# transmitter.net
KiCad netlist of a schematic drawn in Altium Designer
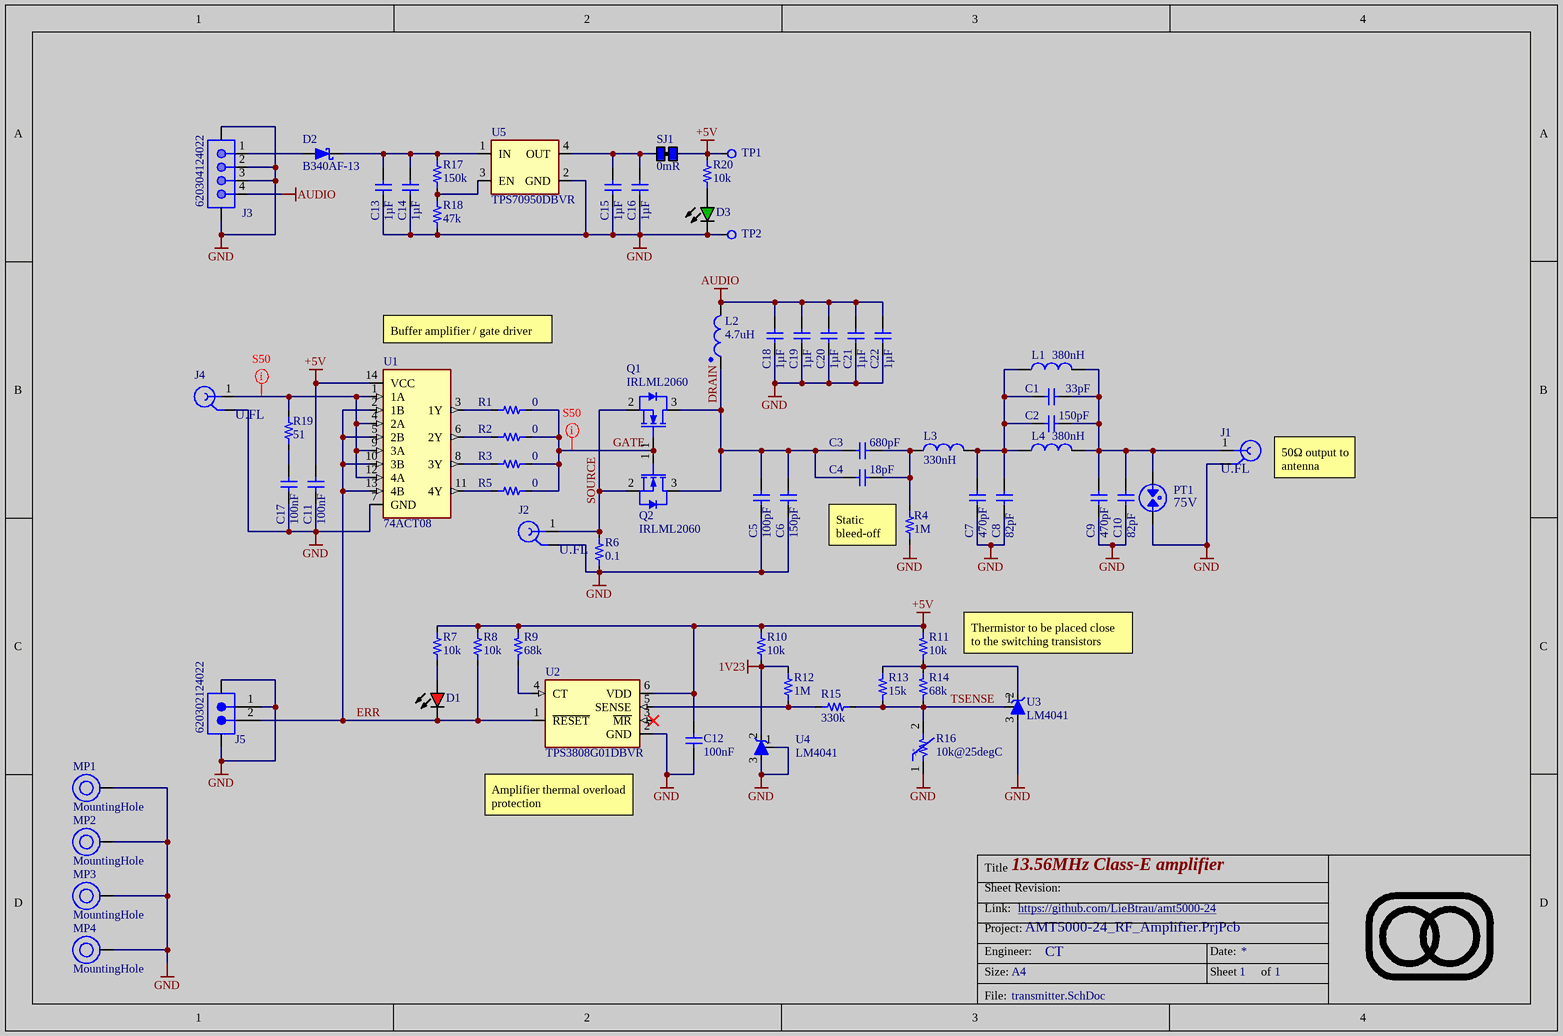
[diagram p0: transmitter.SchDoc]

(export (version "E")
  (design (tool "Eeschema 10.0.6"))
  (components
    (comp (ref "C1")
      (value "33pF")
      (footprint "1206-C-N")
      (description "WCAP-CSGP Multilayer Ceramic Chip Capacitor, General Purpose, size 1206, NP0, 33pF, 50VDC")
      (fields (field (name "TOLERANCE") "5%") (field (name "JLCPCB PART #") "C571053"))
      (libsource (lib "7c7 Engineering") (part "CAP-NP-2"))
    )
    (comp (ref "C2")
      (value "150pF")
      (footprint "1206-C-N")
      (description "WCAP-CSGP Multilayer Ceramic Chip Capacitor, General Purpose, size 1206, NP0, 150pF, 100VDC")
      (fields (field (name "TOLERANCE") "5%") (field (name "JLCPCB PART #") "C162445"))
      (libsource (lib "7c7 Engineering") (part "CAP-NP-2"))
    )
    (comp (ref "C3")
      (value "680pF")
      (footprint "1206-C-N")
      (description "WCAP-CSGP Multilayer Ceramic Chip Capacitor, General Purpose, size 1206, NP0, 680pF, 100VDC")
      (fields (field (name "TOLERANCE") "5%") (field (name "JLCPCB PART #") "C541497"))
      (libsource (lib "7c7 Engineering") (part "CAP-NP-2"))
    )
    (comp (ref "C4")
      (value "18pF")
      (footprint "1206-C-N")
      (description "Surface Mount Ceramic Multilayer Capacitor 18pF 5% C0G 1kV 1206 Blister T/R")
      (fields (field (name "TOLERANCE") "5%") (field (name "JLCPCB PART #") "C33039"))
      (libsource (lib "7c7 Engineering") (part "CAP-NP-2"))
    )
    (comp (ref "C5")
      (value "100pF")
      (footprint "1206-C-N")
      (fields
        (field (name "JLCPCB PART #") "C9188")
        (field (name "TOLERANCE") "5%")
        (field (name "Comment") "Capacitor 100pF +/-5% 630V NP0 Class I 1206")
      )
      (libsource (lib "7c7 Engineering") (part "CAP-NP-2"))
    )
    (comp (ref "C6")
      (value "150pF")
      (footprint "1206-C-N")
      (description "WCAP-CSGP Multilayer Ceramic Chip Capacitor, General Purpose, size 1206, NP0, 150pF, 100VDC")
      (fields (field (name "TOLERANCE") "5%") (field (name "JLCPCB PART #") "C162445"))
      (libsource (lib "7c7 Engineering") (part "CAP-NP-2"))
    )
    (comp (ref "C7")
      (value "470pF")
      (footprint "1206-C-N")
      (description "WCAP-CSGP Multilayer Ceramic Chip Capacitor, General Purpose, size 1206, NP0, 470pF, 100VDC")
      (fields (field (name "TOLERANCE") "5%") (field (name "JLCPCB PART #") "C107177"))
      (libsource (lib "7c7 Engineering") (part "CAP-NP-2"))
    )
    (comp (ref "C8")
      (value "82pF")
      (footprint "1206-C-N")
      (description "Cap Ceramic 82pF 1000V C0G 5% Pad SMD 1206 125C T/R")
      (fields (field (name "JLCPCB PART #") "C396810") (field (name "Comment") "1206N820J102CT"))
      (libsource (lib "7c7 Engineering") (part "CAP-NP-2"))
    )
    (comp (ref "C9")
      (value "470pF")
      (footprint "1206-C-N")
      (description "WCAP-CSGP Multilayer Ceramic Chip Capacitor, General Purpose, size 1206, NP0, 470pF, 100VDC")
      (fields (field (name "TOLERANCE") "5%") (field (name "JLCPCB PART #") "C107177"))
      (libsource (lib "7c7 Engineering") (part "CAP-NP-2"))
    )
    (comp (ref "C10")
      (value "82pF")
      (footprint "1206-C-N")
      (description "Cap Ceramic 82pF 1000V C0G 5% Pad SMD 1206 125C T/R")
      (fields (field (name "JLCPCB PART #") "C396810") (field (name "Comment") "1206N820J102CT"))
      (libsource (lib "7c7 Engineering") (part "CAP-NP-2"))
    )
    (comp (ref "C11")
      (value "100nF")
      (footprint "0603-C-N")
      (description "WCAP-CSGP Multilayer Ceramic Chip Capacitor, General Purpose, size 0603, X7R, 100nF, 50VDC")
      (fields (field (name "TOLERANCE") "10%") (field (name "JLCPCB PART #") "C14663"))
      (libsource (lib "7c7 Engineering") (part "CAP-NP-2"))
    )
    (comp (ref "C12")
      (value "100nF")
      (footprint "0603-C-N")
      (description "WCAP-CSGP Multilayer Ceramic Chip Capacitor, General Purpose, size 0603, X7R, 100nF, 50VDC")
      (fields (field (name "TOLERANCE") "10%") (field (name "JLCPCB PART #") "C14663"))
      (libsource (lib "7c7 Engineering") (part "CAP-NP-2"))
    )
    (comp (ref "C13")
      (value "1µF")
      (footprint "1206-C-N")
      (description "WCAP-CSGP Multilayer Ceramic Chip Capacitor, General Purpose, size 1206, X7R, 1µF, 50VDC")
      (fields (field (name "TOLERANCE") "10%") (field (name "PAGE PART #") "CCOK105"))
      (libsource (lib "7c7 Engineering") (part "CAP-NP-2"))
    )
    (comp (ref "C14")
      (value "1µF")
      (footprint "1206-C-N")
      (description "WCAP-CSGP Multilayer Ceramic Chip Capacitor, General Purpose, size 1206, X7R, 1µF, 50VDC")
      (fields (field (name "TOLERANCE") "10%") (field (name "PAGE PART #") "CCOK105"))
      (libsource (lib "7c7 Engineering") (part "CAP-NP-2"))
    )
    (comp (ref "C15")
      (value "1µF")
      (footprint "1206-C-N")
      (description "WCAP-CSGP Multilayer Ceramic Chip Capacitor, General Purpose, size 1206, X7R, 1µF, 50VDC")
      (fields (field (name "TOLERANCE") "10%") (field (name "PAGE PART #") "CCOK105"))
      (libsource (lib "7c7 Engineering") (part "CAP-NP-2"))
    )
    (comp (ref "C16")
      (value "1µF")
      (footprint "1206-C-N")
      (description "WCAP-CSGP Multilayer Ceramic Chip Capacitor, General Purpose, size 1206, X7R, 1µF, 50VDC")
      (fields (field (name "TOLERANCE") "10%") (field (name "PAGE PART #") "CCOK105"))
      (libsource (lib "7c7 Engineering") (part "CAP-NP-2"))
    )
    (comp (ref "C17")
      (value "100nF")
      (footprint "0603-C-N")
      (description "WCAP-CSGP Multilayer Ceramic Chip Capacitor, General Purpose, size 0603, X7R, 100nF, 50VDC")
      (fields (field (name "TOLERANCE") "10%") (field (name "JLCPCB PART #") "C14663"))
      (libsource (lib "7c7 Engineering") (part "CAP-NP-2"))
    )
    (comp (ref "C18")
      (value "1µF")
      (footprint "1206-C-N")
      (description "WCAP-CSGP Multilayer Ceramic Chip Capacitor, General Purpose, size 1206, X7R, 1µF, 50VDC")
      (fields (field (name "TOLERANCE") "10%") (field (name "PAGE PART #") "CCOK105"))
      (libsource (lib "7c7 Engineering") (part "CAP-NP-2"))
    )
    (comp (ref "C19")
      (value "1µF")
      (footprint "1206-C-N")
      (description "WCAP-CSGP Multilayer Ceramic Chip Capacitor, General Purpose, size 1206, X7R, 1µF, 50VDC")
      (fields (field (name "TOLERANCE") "10%") (field (name "PAGE PART #") "CCOK105"))
      (libsource (lib "7c7 Engineering") (part "CAP-NP-2"))
    )
    (comp (ref "C20")
      (value "1µF")
      (footprint "1206-C-N")
      (description "WCAP-CSGP Multilayer Ceramic Chip Capacitor, General Purpose, size 1206, X7R, 1µF, 50VDC")
      (fields (field (name "TOLERANCE") "10%") (field (name "PAGE PART #") "CCOK105"))
      (libsource (lib "7c7 Engineering") (part "CAP-NP-2"))
    )
    (comp (ref "C21")
      (value "1µF")
      (footprint "1206-C-N")
      (description "WCAP-CSGP Multilayer Ceramic Chip Capacitor, General Purpose, size 1206, X7R, 1µF, 50VDC")
      (fields (field (name "TOLERANCE") "10%") (field (name "PAGE PART #") "CCOK105"))
      (libsource (lib "7c7 Engineering") (part "CAP-NP-2"))
    )
    (comp (ref "C22")
      (value "1µF")
      (footprint "1206-C-N")
      (description "WCAP-CSGP Multilayer Ceramic Chip Capacitor, General Purpose, size 1206, X7R, 1µF, 50VDC")
      (fields (field (name "TOLERANCE") "10%") (field (name "PAGE PART #") "CCOK105"))
      (libsource (lib "7c7 Engineering") (part "CAP-NP-2"))
    )
    (comp (ref "D1")
      (value "150060RS86000")
      (footprint "WL-SMCW_0603_150060xx8x000")
      (description "WL-SMCW Mono-color Chip LED Waterclear, size 0603, Red, 2V, 60°")
      (fields (field (name "JLCPCB PART #") "C5875741") (field (name "MANUFACTURER") "Wurth Elektronik"))
      (libsource (lib "7c7 Engineering") (part "LED-RED-2"))
    )
    (comp (ref "D2")
      (value "B340AF-13")
      (footprint "DO-214AC_UNI")
      (description "Diode 40 V 3A Surface Mount SMAF")
      (fields (field (name "JLCPCB PART #") "C172880"))
      (libsource (lib "7c7 Engineering") (part "DIODE-SKY-2"))
    )
    (comp (ref "D3")
      (value "150060GS84000")
      (footprint "WL-SMCW_0603_150060xx8x000")
      (description "WL-SMCW Mono-color Chip LED Waterclear, size 0603, Green, 3.3V, 40°")
      (fields (field (name "JLCPCB PART #") "C965804") (field (name "MANUFACTURER") "Wurth Elektronik"))
      (libsource (lib "7c7 Engineering") (part "LED-GREEN-2"))
    )
    (comp (ref "J1")
      (value "U.FL-R-SMT(10)")
      (footprint "HRS-U.FL-R-SMT_V")
      (fields (field (name "JLCPCB PART #") "C88373") (field (name "MANUFACTURER") "Hirose Electric"))
      (libsource (lib "7c7 Engineering") (part "CN_COAX"))
    )
    (comp (ref "J2")
      (value "U.FL-R-SMT(10)")
      (footprint "HRS-U.FL-R-SMT_V")
      (fields (field (name "JLCPCB PART #") "C88373") (field (name "MANUFACTURER") "Hirose Electric"))
      (libsource (lib "") (part "CN_COAX_1"))
    )
    (comp (ref "J3")
      (value "620304124022")
      (footprint "620304124022")
      (description "WR-WTB SMT Male Vertical Shrouded Header, pitch 2mm, 4p")
      (fields (field (name "JLCPCB PART #") "C160354") (field (name "PUBLISHER") "Wurth Elektronik"))
      (libsource (lib "7c7 Engineering") (part "HDR_4P_2MP"))
    )
    (comp (ref "J4")
      (value "U.FL-R-SMT(10)")
      (footprint "HRS-U.FL-R-SMT_V")
      (fields (field (name "JLCPCB PART #") "C88373") (field (name "MANUFACTURER") "Hirose Electric"))
      (libsource (lib "") (part "CN_COAX_1"))
    )
    (comp (ref "J5")
      (value "620302124022")
      (footprint "620302124022")
      (description "WR-WTB SMT Male Vertical Shrouded Header, pitch 2mm, 2p")
      (fields (field (name "JLCPCB PART #") "C160352") (field (name "PUBLISHER") "Wurth Elektronik"))
      (libsource (lib "7c7 Engineering") (part "HDR_2P_2MP"))
    )
    (comp (ref "L1")
      (value "744918238")
      (footprint "WE-CAIR_5910")
      (description "WE-CAIR SMT Air Coil, size 5910, 380nH, 2.5A, 50mO")
      (fields (field (name "MANUFACTURER") "Wurth Elektronik") (field (name "INDUCTANCE") "380nH"))
      (libsource (lib "7c7 Engineering") (part "IND"))
    )
    (comp (ref "L2")
      (value "784771047")
      (footprint "WE-PDA_1260")
      (description "WE-PDA SMT Shielded Power Inductor, size 1260, 4.7uH, 6.2A, 17.5mOhm")
      (fields (field (name "MANUFACTURER") "Wurth Elektronik") (field (name "INDUCTANCE") "4.7uH"))
      (libsource (lib "7c7 Engineering") (part "IND_POLAR-2"))
    )
    (comp (ref "L3")
      (value "330nH")
      (footprint "IND_2929SQ-331")
      (description "RF inductor, air core, 2% tol, SMT, RoHS, halogen-free")
      (fields (field (name "TOLERANCE") "2%") (field (name "JLCPCB PART #") "C20623511"))
      (libsource (lib "7c7 Engineering") (part "IND"))
    )
    (comp (ref "L4")
      (value "744918238")
      (footprint "WE-CAIR_5910")
      (description "WE-CAIR SMT Air Coil, size 5910, 380nH, 2.5A, 50mO")
      (fields (field (name "MANUFACTURER") "Wurth Elektronik") (field (name "INDUCTANCE") "380nH"))
      (libsource (lib "7c7 Engineering") (part "IND"))
    )
    (comp (ref "MP1")
      (value "MountingHole")
      (footprint "PTH-M3D6.5_VIA-RING")
      (libsource (lib "7c7 Engineering") (part "MECH_NO_BOM"))
    )
    (comp (ref "MP2")
      (value "MountingHole")
      (footprint "PTH-M3D6.5_VIA-RING")
      (libsource (lib "7c7 Engineering") (part "MECH_NO_BOM"))
    )
    (comp (ref "MP3")
      (value "MountingHole")
      (footprint "PTH-M3D6.5_VIA-RING")
      (libsource (lib "7c7 Engineering") (part "MECH_NO_BOM"))
    )
    (comp (ref "MP4")
      (value "MountingHole")
      (footprint "PTH-M3D6.5_VIA-RING")
      (libsource (lib "7c7 Engineering") (part "MECH_NO_BOM"))
    )
    (comp (ref "PT1")
      (value "GTCC23-750M-R01-2")
      (footprint "GDT_4532")
      (description "Gas Discharge Tubes - GDTs / Gas Plasma Arrestors 75VDC 2-POLE 600V @1KV/US")
      (fields (field (name "JLCPCB PART #") "C9234") (field (name "TOLERANCE") "20%"))
      (libsource (lib "7c7 Engineering") (part "PT_GDT"))
    )
    (comp (ref "Q1")
      (value "IRLML2060")
      (footprint "SOT-23-3-N")
      (description "60V Single N-Channel HEXFET Power MOSFET in a Micro 3 package, SOT23-3, RoHS")
      (fields (field (name "JLCPCB PART #") "C67275") (field (name "Comment") "IRLML2060TRPBF"))
      (libsource (lib "7c7 Engineering") (part "NEMOS-GSD-3"))
    )
    (comp (ref "Q2")
      (value "IRLML2060")
      (footprint "SOT-23-3-N")
      (description "60V Single N-Channel HEXFET Power MOSFET in a Micro 3 package, SOT23-3, RoHS")
      (fields (field (name "JLCPCB PART #") "C67275") (field (name "Comment") "IRLML2060TRPBF"))
      (libsource (lib "7c7 Engineering") (part "NEMOS-GSD-3"))
    )
    (comp (ref "R1")
      (value "0")
      (footprint "0603-R-N")
      (description "Chip Jumper, Thick Film, Jumper, 0603, 100mW, 1A, 0 Ohm, <50 mOhm")
      (fields (field (name "FLIR PART #") "YRES0E-1") (field (name "TOLERANCE") "50 mOhm"))
      (libsource (lib "7c7 Engineering") (part "RES"))
    )
    (comp (ref "R2")
      (value "0")
      (footprint "0603-R-N")
      (description "Chip Jumper, Thick Film, Jumper, 0603, 100mW, 1A, 0 Ohm, <50 mOhm")
      (fields (field (name "FLIR PART #") "YRES0E-1") (field (name "TOLERANCE") "50 mOhm"))
      (libsource (lib "7c7 Engineering") (part "RES"))
    )
    (comp (ref "R3")
      (value "0")
      (footprint "0603-R-N")
      (description "Chip Jumper, Thick Film, Jumper, 0603, 100mW, 1A, 0 Ohm, <50 mOhm")
      (fields (field (name "FLIR PART #") "YRES0E-1") (field (name "TOLERANCE") "50 mOhm"))
      (libsource (lib "7c7 Engineering") (part "RES"))
    )
    (comp (ref "R4")
      (value "1M")
      (footprint "1206-R-N")
      (description "Res Thick Film 1206 1M Ohm 1% 0.25W(1/4W) ±100ppm/C SMD T/R")
      (fields (field (name "JLCPCB PART #") "C17927") (field (name "TOLERANCE") "1%"))
      (libsource (lib "7c7 Engineering") (part "RES"))
    )
    (comp (ref "R5")
      (value "0")
      (footprint "0603-R-N")
      (description "Chip Jumper, Thick Film, Jumper, 0603, 100mW, 1A, 0 Ohm, <50 mOhm")
      (fields (field (name "FLIR PART #") "YRES0E-1") (field (name "TOLERANCE") "50 mOhm"))
      (libsource (lib "7c7 Engineering") (part "RES"))
    )
    (comp (ref "R6")
      (value "0.1")
      (footprint "1206-R-N")
      (description "Res Thick Film 1206 0.1 Ohm 1% 1/2W ±100ppm/°C Molded SMD SMD Paper T/R")
      (fields (field (name "JLCPCB PART #") "C346763") (field (name "TOLERANCE") "1%"))
      (libsource (lib "7c7 Engineering") (part "RES"))
    )
    (comp (ref "R7")
      (value "10k")
      (footprint "0603-R-N")
      (description "Chip Resistor, Thick Film, General Purpose, 0603, 100mW, 50V, 10 kOhm, +/-1%")
      (fields (field (name "JLCPCB PART #") "C25804") (field (name "FLIR PART #") "YRES10K-1"))
      (libsource (lib "7c7 Engineering") (part "RES"))
    )
    (comp (ref "R8")
      (value "10k")
      (footprint "0603-R-N")
      (description "Chip Resistor, Thick Film, General Purpose, 0603, 100mW, 50V, 10 kOhm, +/-1%")
      (fields (field (name "JLCPCB PART #") "C25804") (field (name "FLIR PART #") "YRES10K-1"))
      (libsource (lib "7c7 Engineering") (part "RES"))
    )
    (comp (ref "R9")
      (value "68k")
      (footprint "0603-R-N")
      (description "Chip Resistor, Thick Film, General Purpose, 0603, 100mW, 50V, 68 kOhm, +/-1%")
      (fields (field (name "TOLERANCE") "1%") (field (name "JLCPCB PART #") "C114633"))
      (libsource (lib "7c7 Engineering") (part "RES"))
    )
    (comp (ref "R10")
      (value "10k")
      (footprint "0603-R-N")
      (description "Chip Resistor, Thick Film, General Purpose, 0603, 100mW, 50V, 10 kOhm, +/-1%")
      (fields (field (name "JLCPCB PART #") "C25804") (field (name "FLIR PART #") "YRES10K-1"))
      (libsource (lib "7c7 Engineering") (part "RES"))
    )
    (comp (ref "R11")
      (value "10k")
      (footprint "0603-R-N")
      (description "Chip Resistor, Thick Film, General Purpose, 0603, 100mW, 50V, 10 kOhm, +/-1%")
      (fields (field (name "JLCPCB PART #") "C25804") (field (name "FLIR PART #") "YRES10K-1"))
      (libsource (lib "7c7 Engineering") (part "RES"))
    )
    (comp (ref "R12")
      (value "1M")
      (footprint "0603-R-N")
      (description "Chip Resistor, Thick Film, General Purpose, 0603, 100mW, 50V, 1 MOhm, +/-1%")
      (fields (field (name "TOLERANCE") "1%") (field (name "JLCPCB PART #") "C22935"))
      (libsource (lib "7c7 Engineering") (part "RES"))
    )
    (comp (ref "R13")
      (value "15k")
      (footprint "0603-R-N")
      (description "Chip Resistor, Thick Film, General Purpose, 0603, 100mW, 50V, 15 kOhm, +/-1%")
      (fields (field (name "JLCPCB PART #") "C22809") (field (name "TOLERANCE") "1%"))
      (libsource (lib "7c7 Engineering") (part "RES"))
    )
    (comp (ref "R14")
      (value "68k")
      (footprint "0603-R-N")
      (description "Chip Resistor, Thick Film, General Purpose, 0603, 100mW, 50V, 68 kOhm, +/-1%")
      (fields (field (name "TOLERANCE") "1%") (field (name "JLCPCB PART #") "C114633"))
      (libsource (lib "7c7 Engineering") (part "RES"))
    )
    (comp (ref "R15")
      (value "330k")
      (footprint "0603-R-N")
      (description "Chip Resistor, Thick Film, General Purpose, 0603, 100mW, 50V, 330 kOhm, +/-1%")
      (fields (field (name "TOLERANCE") "1%") (field (name "JLCPCB PART #") "C23137"))
      (libsource (lib "7c7 Engineering") (part "RES"))
    )
    (comp (ref "R16")
      (value "10k@25degC")
      (footprint "0603-R-N")
      (description "Thermistor NTC 10K Ohm 5% 2-Pin 0603 Surface Mount Solder Pad 3450K T/R")
      (fields (field (name "TOLERANCE") "1%") (field (name "JLCPCB PART #") "C13564"))
      (libsource (lib "7c7 Engineering") (part "RES-NTC"))
    )
    (comp (ref "R17")
      (value "150k")
      (footprint "0603-R-N")
      (description "Chip Resistor, Thick Film, General Purpose, 0603, 100mW, 50V, 150 kOhm, +/-1%")
      (fields (field (name "FLIR PART #") "YRES150K-1") (field (name "JLCPCB PART #") "C22807"))
      (libsource (lib "7c7 Engineering") (part "RES"))
    )
    (comp (ref "R18")
      (value "47k")
      (footprint "0603-R-N")
      (description "Chip Resistor, Thick Film, General Purpose, 0603, 100mW, 50V, 47 kOhm, +/-1%")
      (fields (field (name "JLCPCB PART #") "C25819") (field (name "TOLERANCE") "1%"))
      (libsource (lib "7c7 Engineering") (part "RES"))
    )
    (comp (ref "R19")
      (value "51")
      (footprint "0603-R-N")
      (description "Res Thick Film 0603 51 Ohm 1% 1/10W ±100ppm/°C Molded SMD SMD Paper T/R")
      (fields (field (name "JLCPCB PART #") "C23197") (field (name "TOLERANCE") "1%"))
      (libsource (lib "7c7 Engineering") (part "RES"))
    )
    (comp (ref "R20")
      (value "10k")
      (footprint "0603-R-N")
      (description "Chip Resistor, Thick Film, General Purpose, 0603, 100mW, 50V, 10 kOhm, +/-1%")
      (fields (field (name "JLCPCB PART #") "C25804") (field (name "FLIR PART #") "YRES10K-1"))
      (libsource (lib "7c7 Engineering") (part "RES"))
    )
    (comp (ref "SJ1")
      (value "0mR")
      (footprint "SJ-0805-2A")
      (description "Zero Ohm Resistor, Jumper, 0805 [2012 Metric], Thick Film, 125 mW, 2 A, Surface Mount")
      (fields (field (name "TOLERANCE") "5%") (field (name "JLCPCB PART #") "C96345"))
      (libsource (lib "7c7 Engineering") (part "SJ-C"))
    )
    (comp (ref "TP1")
      (value "Testpad with multiple sizes")
      (footprint "TP_1.5mm_0.3mmHole")
      (description "Testpad land")
      (libsource (lib "7c7 Engineering") (part "Testpad"))
    )
    (comp (ref "TP2")
      (value "Testpad with multiple sizes")
      (footprint "TP_1.5mm_0.3mmHole")
      (description "Testpad land")
      (libsource (lib "7c7 Engineering") (part "Testpad"))
    )
    (comp (ref "U1")
      (value "74ACT08")
      (footprint "FP-PW0014A-MFG")
      (description "4-ch, 2-input, 4.5-V to 5.5-V AND gates with TTL-compatible CMOS inputs 14-TSSOP -40 to 85")
      (fields (field (name "JLCPCB PART #") "C544637") (field (name "Comment") "SN74ACT08PWR"))
      (libsource (lib "7c7 Engineering") (part "74xx08"))
    )
    (comp (ref "U2")
      (value "TPS3808G01DBVR")
      (footprint "SOT-23-6")
      (description "Supervisor Open Drain or Open Collector 1 Channel SOT-23-6")
      (fields (field (name "JLCPCB PART #") "C19653"))
      (libsource (lib "7c7 Engineering") (part "TPS3808G01DBV6"))
    )
    (comp (ref "U3")
      (value "LM4041")
      (footprint "SOT-23-3-N")
      (description "Fixed & adjustable, 45-µA, precision micropower shunt voltage reference 3-SOT-23 -40 to 85")
      (fields (field (name "JLCPCB PART #") "C2156756") (field (name "TOLERANCE") "1%"))
      (libsource (lib "7c7 Engineering") (part "IC_TLV431"))
    )
    (comp (ref "U4")
      (value "LM4041")
      (footprint "SOT-23-3-N")
      (description "Fixed & adjustable, 45-µA, precision micropower shunt voltage reference 3-SOT-23 -40 to 85")
      (fields (field (name "JLCPCB PART #") "C2156756") (field (name "TOLERANCE") "1%"))
      (libsource (lib "7c7 Engineering") (part "IC_TLV431"))
    )
    (comp (ref "U5")
      (value "TPS70950DBVR")
      (footprint "SOT25-N")
      (description "Linear Voltage Regulator IC Positive Fixed 1 Output 5V 150mA SOT-23-5")
      (fields (field (name "JLCPCB PART #") "C96028"))
      (libsource (lib "7c7 Engineering") (part "LDO-with-enable"))
    )
  )
  (nets
    (net (code "1") (name "+5V") (class "Default")
      (node (ref "C11") (pin "2") (pinfunction "2_2") (pintype "passive"))
      (node (ref "C12") (pin "2") (pinfunction "2_2") (pintype "passive"))
      (node (ref "R10") (pin "2") (pinfunction "2_2") (pintype "passive"))
      (node (ref "R11") (pin "2") (pinfunction "2_2") (pintype "passive"))
      (node (ref "R20") (pin "2") (pinfunction "2_2") (pintype "passive"))
      (node (ref "R7") (pin "2") (pinfunction "2_2") (pintype "passive"))
      (node (ref "R8") (pin "2") (pinfunction "2_2") (pintype "passive"))
      (node (ref "R9") (pin "1") (pinfunction "1_1") (pintype "passive"))
      (node (ref "SJ1") (pin "2") (pinfunction "R_2") (pintype "passive"))
      (node (ref "TP1") (pin "1") (pinfunction "Pad_1") (pintype "passive"))
      (node (ref "U1") (pin "14") (pinfunction "VCC_14") (pintype "power_in"))
      (node (ref "U2") (pin "6") (pinfunction "VDD_6") (pintype "power_in"))
    )
    (net (code "2") (name "/DRAIN") (class "Default")
      (node (ref "C3") (pin "1") (pinfunction "1_1") (pintype "passive"))
      (node (ref "C4") (pin "1") (pinfunction "1_1") (pintype "passive"))
      (node (ref "C5") (pin "2") (pinfunction "2_2") (pintype "passive"))
      (node (ref "C6") (pin "2") (pinfunction "2_2") (pintype "passive"))
      (node (ref "L2") (pin "1") (pinfunction "1_1") (pintype "passive"))
      (node (ref "Q1") (pin "3") (pinfunction "D_3") (pintype "passive"))
      (node (ref "Q2") (pin "3") (pinfunction "D_3") (pintype "passive"))
    )
    (net (code "3") (name "/ERR") (class "Default")
      (node (ref "D1") (pin "1") (pinfunction "K_1") (pintype "passive"))
      (node (ref "J5") (pin "2") (pinfunction "2_2") (pintype "passive"))
      (node (ref "R8") (pin "1") (pinfunction "1_1") (pintype "passive"))
      (node (ref "U1") (pin "10") (pinfunction "3B_10") (pintype "input"))
      (node (ref "U1") (pin "13") (pinfunction "4B_13") (pintype "input"))
      (node (ref "U1") (pin "2") (pinfunction "1B_2") (pintype "input"))
      (node (ref "U1") (pin "5") (pinfunction "2B_5") (pintype "input"))
      (node (ref "U2") (pin "1") (pinfunction "~{RESET}_1") (pintype "tri_state"))
    )
    (net (code "4") (name "/GATE") (class "Default")
      (node (ref "Q1") (pin "1") (pinfunction "G_1") (pintype "passive"))
      (node (ref "Q2") (pin "1") (pinfunction "G_1") (pintype "passive"))
      (node (ref "R1") (pin "2") (pinfunction "2_2") (pintype "passive"))
      (node (ref "R2") (pin "2") (pinfunction "2_2") (pintype "passive"))
      (node (ref "R3") (pin "2") (pinfunction "2_2") (pintype "passive"))
      (node (ref "R5") (pin "2") (pinfunction "2_2") (pintype "passive"))
    )
    (net (code "5") (name "/SOURCE") (class "Default")
      (node (ref "J2") (pin "1") (pinfunction "SIG_1") (pintype "passive"))
      (node (ref "Q1") (pin "2") (pinfunction "S_2") (pintype "passive"))
      (node (ref "Q2") (pin "2") (pinfunction "S_2") (pintype "passive"))
      (node (ref "R6") (pin "1") (pinfunction "1_1") (pintype "passive"))
    )
    (net (code "6") (name "/TSENSE") (class "Default")
      (node (ref "R13") (pin "1") (pinfunction "1_1") (pintype "passive"))
      (node (ref "R14") (pin "1") (pinfunction "1_1") (pintype "passive"))
      (node (ref "R15") (pin "2") (pinfunction "2_2") (pintype "passive"))
      (node (ref "R16") (pin "2") (pinfunction "2_2") (pintype "passive"))
      (node (ref "U3") (pin "1") (pinfunction "rEF_1") (pintype "passive"))
    )
    (net (code "7") (name "1V23") (class "Default")
      (node (ref "R10") (pin "1") (pinfunction "1_1") (pintype "passive"))
      (node (ref "R12") (pin "2") (pinfunction "2_2") (pintype "passive"))
      (node (ref "U4") (pin "2") (pinfunction "C_2") (pintype "power_in"))
    )
    (net (code "8") (name "AUDIO") (class "Default")
      (node (ref "C18") (pin "2") (pinfunction "2_2") (pintype "passive"))
      (node (ref "C19") (pin "2") (pinfunction "2_2") (pintype "passive"))
      (node (ref "C20") (pin "2") (pinfunction "2_2") (pintype "passive"))
      (node (ref "C21") (pin "2") (pinfunction "2_2") (pintype "passive"))
      (node (ref "C22") (pin "2") (pinfunction "2_2") (pintype "passive"))
      (node (ref "J3") (pin "4") (pinfunction "4_4") (pintype "passive"))
      (node (ref "L2") (pin "2") (pinfunction "2_2") (pintype "passive"))
    )
    (net (code "9") (name "GND") (class "Default")
      (node (ref "C10") (pin "1") (pinfunction "1_1") (pintype "passive"))
      (node (ref "C11") (pin "1") (pinfunction "1_1") (pintype "passive"))
      (node (ref "C12") (pin "1") (pinfunction "1_1") (pintype "passive"))
      (node (ref "C13") (pin "1") (pinfunction "1_1") (pintype "passive"))
      (node (ref "C14") (pin "1") (pinfunction "1_1") (pintype "passive"))
      (node (ref "C15") (pin "1") (pinfunction "1_1") (pintype "passive"))
      (node (ref "C16") (pin "1") (pinfunction "1_1") (pintype "passive"))
      (node (ref "C17") (pin "1") (pinfunction "1_1") (pintype "passive"))
      (node (ref "C18") (pin "1") (pinfunction "1_1") (pintype "passive"))
      (node (ref "C19") (pin "1") (pinfunction "1_1") (pintype "passive"))
      (node (ref "C20") (pin "1") (pinfunction "1_1") (pintype "passive"))
      (node (ref "C21") (pin "1") (pinfunction "1_1") (pintype "passive"))
      (node (ref "C22") (pin "1") (pinfunction "1_1") (pintype "passive"))
      (node (ref "C5") (pin "1") (pinfunction "1_1") (pintype "passive"))
      (node (ref "C6") (pin "1") (pinfunction "1_1") (pintype "passive"))
      (node (ref "C7") (pin "1") (pinfunction "1_1") (pintype "passive"))
      (node (ref "C8") (pin "1") (pinfunction "1_1") (pintype "passive"))
      (node (ref "C9") (pin "1") (pinfunction "1_1") (pintype "passive"))
      (node (ref "D3") (pin "1") (pinfunction "K_1") (pintype "passive"))
      (node (ref "J1") (pin "2") (pinfunction "GND_2") (pintype "passive"))
      (node (ref "J2") (pin "2") (pinfunction "GND_2") (pintype "passive"))
      (node (ref "J3") (pin "2") (pinfunction "2_2") (pintype "passive"))
      (node (ref "J3") (pin "3") (pinfunction "3_3") (pintype "passive"))
      (node (ref "J3") (pin "MP1") (pinfunction "MP1_MP1") (pintype "power_in"))
      (node (ref "J3") (pin "MP2") (pinfunction "MP2_MP2") (pintype "power_in"))
      (node (ref "J4") (pin "2") (pinfunction "GND_2") (pintype "passive"))
      (node (ref "J5") (pin "1") (pinfunction "1_1") (pintype "passive"))
      (node (ref "J5") (pin "MP1") (pinfunction "MP1_MP1") (pintype "passive"))
      (node (ref "J5") (pin "MP2") (pinfunction "MP2_MP2") (pintype "passive"))
      (node (ref "MP1") (pin "1") (pinfunction "H1_1") (pintype "passive"))
      (node (ref "MP2") (pin "1") (pinfunction "H1_1") (pintype "passive"))
      (node (ref "MP3") (pin "1") (pinfunction "H1_1") (pintype "passive"))
      (node (ref "MP4") (pin "1") (pinfunction "H1_1") (pintype "passive"))
      (node (ref "PT1") (pin "2") (pinfunction "2_2") (pintype "passive"))
      (node (ref "R16") (pin "1") (pinfunction "1_1") (pintype "passive"))
      (node (ref "R18") (pin "2") (pinfunction "2_2") (pintype "passive"))
      (node (ref "R4") (pin "1") (pinfunction "1_1") (pintype "passive"))
      (node (ref "R6") (pin "2") (pinfunction "2_2") (pintype "passive"))
      (node (ref "TP2") (pin "1") (pinfunction "Pad_1") (pintype "passive"))
      (node (ref "U1") (pin "7") (pinfunction "GND_7") (pintype "power_in"))
      (node (ref "U2") (pin "2") (pinfunction "GND_2") (pintype "power_in"))
      (node (ref "U3") (pin "3") (pinfunction "A_3") (pintype "power_in"))
      (node (ref "U4") (pin "1") (pinfunction "rEF_1") (pintype "passive"))
      (node (ref "U4") (pin "3") (pinfunction "A_3") (pintype "power_in"))
      (node (ref "U5") (pin "2") (pinfunction "GND_2") (pintype "power_in"))
    )
    (net (code "10") (name "Net-(C1-Pad1)") (class "Default")
      (node (ref "C1") (pin "1") (pinfunction "1_1") (pintype "passive"))
      (node (ref "C2") (pin "2") (pinfunction "2_2") (pintype "passive"))
      (node (ref "C7") (pin "2") (pinfunction "2_2") (pintype "passive"))
      (node (ref "C8") (pin "2") (pinfunction "2_2") (pintype "passive"))
      (node (ref "L1") (pin "1") (pinfunction "1_1") (pintype "passive"))
      (node (ref "L3") (pin "2") (pinfunction "2_2") (pintype "passive"))
      (node (ref "L4") (pin "1") (pinfunction "1_1") (pintype "passive"))
    )
    (net (code "11") (name "Net-(C3-Pad2)") (class "Default")
      (node (ref "C3") (pin "2") (pinfunction "2_2") (pintype "passive"))
      (node (ref "C4") (pin "2") (pinfunction "2_2") (pintype "passive"))
      (node (ref "L3") (pin "1") (pinfunction "1_1") (pintype "passive"))
      (node (ref "R4") (pin "2") (pinfunction "2_2") (pintype "passive"))
    )
    (net (code "12") (name "Net-(C17-Pad2)") (class "Default")
      (node (ref "C17") (pin "2") (pinfunction "2_2") (pintype "passive"))
      (node (ref "R19") (pin "1") (pinfunction "1_1") (pintype "passive"))
    )
    (net (code "13") (name "Net-(D1-A)") (class "Default")
      (node (ref "D1") (pin "2") (pinfunction "A_2") (pintype "passive"))
      (node (ref "R7") (pin "1") (pinfunction "1_1") (pintype "passive"))
    )
    (net (code "14") (name "Net-(D2-A)") (class "Default")
      (node (ref "D2") (pin "2") (pinfunction "A_2") (pintype "passive"))
      (node (ref "J3") (pin "1") (pinfunction "1_1") (pintype "passive"))
    )
    (net (code "15") (name "Net-(D2-K)") (class "Default")
      (node (ref "C13") (pin "2") (pinfunction "2_2") (pintype "passive"))
      (node (ref "C14") (pin "2") (pinfunction "2_2") (pintype "passive"))
      (node (ref "D2") (pin "1") (pinfunction "K_1") (pintype "passive"))
      (node (ref "R17") (pin "1") (pinfunction "1_1") (pintype "passive"))
      (node (ref "U5") (pin "1") (pinfunction "IN_1") (pintype "power_in"))
    )
    (net (code "16") (name "Net-(D3-A)") (class "Default")
      (node (ref "D3") (pin "2") (pinfunction "A_2") (pintype "passive"))
      (node (ref "R20") (pin "1") (pinfunction "1_1") (pintype "passive"))
    )
    (net (code "17") (name "Net-(J1-SIG)") (class "Default")
      (node (ref "C1") (pin "2") (pinfunction "2_2") (pintype "passive"))
      (node (ref "C10") (pin "2") (pinfunction "2_2") (pintype "passive"))
      (node (ref "C2") (pin "1") (pinfunction "1_1") (pintype "passive"))
      (node (ref "C9") (pin "2") (pinfunction "2_2") (pintype "passive"))
      (node (ref "J1") (pin "1") (pinfunction "SIG_1") (pintype "passive"))
      (node (ref "L1") (pin "2") (pinfunction "2_2") (pintype "passive"))
      (node (ref "L4") (pin "2") (pinfunction "2_2") (pintype "passive"))
      (node (ref "PT1") (pin "1") (pinfunction "1_1") (pintype "passive"))
    )
    (net (code "18") (name "Net-(J4-SIG)") (class "Default")
      (node (ref "J4") (pin "1") (pinfunction "SIG_1") (pintype "passive"))
      (node (ref "R19") (pin "2") (pinfunction "2_2") (pintype "passive"))
      (node (ref "U1") (pin "1") (pinfunction "1A_1") (pintype "input"))
      (node (ref "U1") (pin "12") (pinfunction "4A_12") (pintype "input"))
      (node (ref "U1") (pin "4") (pinfunction "2A_4") (pintype "input"))
      (node (ref "U1") (pin "9") (pinfunction "3A_9") (pintype "input"))
    )
    (net (code "19") (name "Net-(SJ1-L)") (class "Default")
      (node (ref "C15") (pin "2") (pinfunction "2_2") (pintype "passive"))
      (node (ref "C16") (pin "2") (pinfunction "2_2") (pintype "passive"))
      (node (ref "SJ1") (pin "1") (pinfunction "L_1") (pintype "passive"))
      (node (ref "U5") (pin "4") (pinfunction "OUT_4") (pintype "power_in"))
    )
    (net (code "20") (name "Net-(U1-1Y)") (class "Default")
      (node (ref "R1") (pin "1") (pinfunction "1_1") (pintype "passive"))
      (node (ref "U1") (pin "3") (pinfunction "1Y_3") (pintype "output"))
    )
    (net (code "21") (name "Net-(U1-2Y)") (class "Default")
      (node (ref "R2") (pin "1") (pinfunction "1_1") (pintype "passive"))
      (node (ref "U1") (pin "6") (pinfunction "2Y_6") (pintype "output"))
    )
    (net (code "22") (name "Net-(U1-3Y)") (class "Default")
      (node (ref "R3") (pin "1") (pinfunction "1_1") (pintype "passive"))
      (node (ref "U1") (pin "8") (pinfunction "3Y_8") (pintype "output"))
    )
    (net (code "23") (name "Net-(U1-4Y)") (class "Default")
      (node (ref "R5") (pin "1") (pinfunction "1_1") (pintype "passive"))
      (node (ref "U1") (pin "11") (pinfunction "4Y_11") (pintype "output"))
    )
    (net (code "24") (name "Net-(U2-CT)") (class "Default")
      (node (ref "R9") (pin "2") (pinfunction "2_2") (pintype "passive"))
      (node (ref "U2") (pin "4") (pinfunction "CT_4") (pintype "input"))
    )
    (net (code "25") (name "Net-(U2-SENSE)") (class "Default")
      (node (ref "R12") (pin "1") (pinfunction "1_1") (pintype "passive"))
      (node (ref "R15") (pin "1") (pinfunction "1_1") (pintype "passive"))
      (node (ref "U2") (pin "5") (pinfunction "SENSE_5") (pintype "input"))
    )
    (net (code "26") (name "Net-(U3-C)") (class "Default")
      (node (ref "R11") (pin "1") (pinfunction "1_1") (pintype "passive"))
      (node (ref "R13") (pin "2") (pinfunction "2_2") (pintype "passive"))
      (node (ref "R14") (pin "2") (pinfunction "2_2") (pintype "passive"))
      (node (ref "U3") (pin "2") (pinfunction "C_2") (pintype "power_in"))
    )
    (net (code "27") (name "Net-(U5-EN)") (class "Default")
      (node (ref "R17") (pin "2") (pinfunction "2_2") (pintype "passive"))
      (node (ref "R18") (pin "1") (pinfunction "1_1") (pintype "passive"))
      (node (ref "U5") (pin "3") (pinfunction "EN_3") (pintype "passive"))
    )
    (net (code "28") (name "unconnected-(U2-~{MR}-Pad3)") (class "Default")
      (node (ref "U2") (pin "3") (pinfunction "~{MR}_3") (pintype "input+no_connect"))
    )
  )
)
